# board.net
KiCad netlist of a schematic drawn in EAGLE
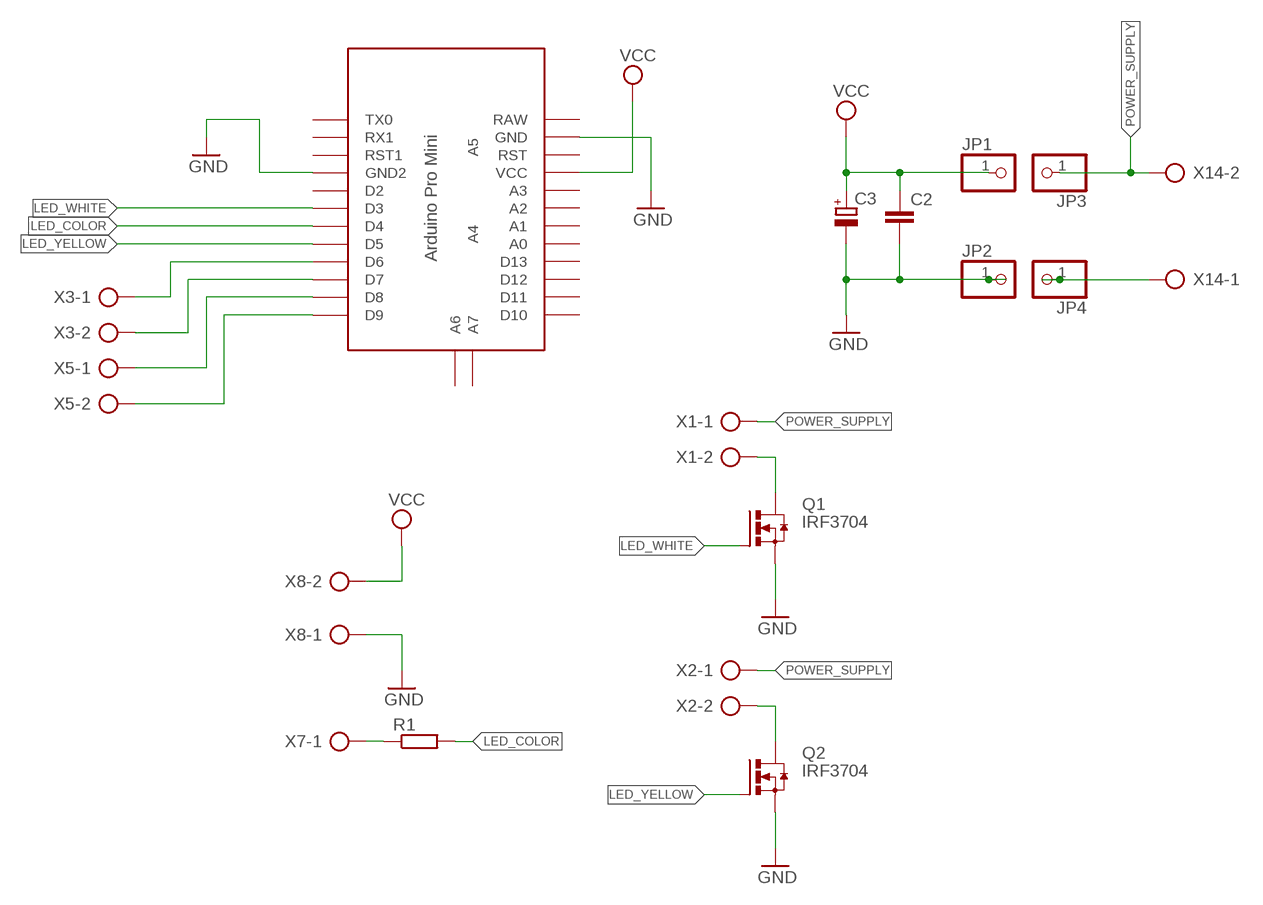
[diagram p0: schematic, sheet 1]

(export (version "E")
  (design (tool "Eeschema 10.0.6"))
  (components
    (comp (ref "C2")
      (value "C-EU050-025X075")
      (footprint "eagle-import:C050-025X075")
      (libsource (lib "eagle-import") (part "C-EU050-025X075"))
    )
    (comp (ref "C3")
      (value "CPOL-EUE3.5-8")
      (footprint "eagle-import:E3,5-8")
      (libsource (lib "eagle-import") (part "CPOL-EUE3.5-8"))
    )
    (comp (ref "JP1")
      (value "PINHD-1X1")
      (footprint "eagle-import:1X01")
      (libsource (lib "eagle-import") (part "PINHD-1X1"))
    )
    (comp (ref "JP2")
      (value "PINHD-1X1")
      (footprint "eagle-import:1X01")
      (libsource (lib "eagle-import") (part "PINHD-1X1"))
    )
    (comp (ref "JP3")
      (value "PINHD-1X1")
      (footprint "eagle-import:1X01")
      (libsource (lib "eagle-import") (part "PINHD-1X1"))
    )
    (comp (ref "JP4")
      (value "PINHD-1X1")
      (footprint "eagle-import:1X01")
      (libsource (lib "eagle-import") (part "PINHD-1X1"))
    )
    (comp (ref "Q1")
      (value "IRF3704")
      (footprint "eagle-import:TO220AH")
      (libsource (lib "eagle-import") (part "IRF3704"))
    )
    (comp (ref "Q2")
      (value "IRF3704")
      (footprint "eagle-import:TO220AH")
      (libsource (lib "eagle-import") (part "IRF3704"))
    )
    (comp (ref "R1")
      (value "R-EU_0204/7")
      (footprint "eagle-import:0204_7")
      (libsource (lib "eagle-import") (part "R-EU_0204/7"))
    )
    (comp (ref "U$1")
      (value "ABK-PRO-MINI")
      (footprint "eagle-import:ABK-PRO-MINI")
      (libsource (lib "eagle-import") (part "ABK-PRO-MINI"))
    )
    (comp (ref "X1")
      (value "AK500/2-H")
      (footprint "eagle-import:AK500_2-H")
      (libsource (lib "eagle-import") (part "AK500/2-H"))
    )
    (comp (ref "X2")
      (value "AK500/2-H")
      (footprint "eagle-import:AK500_2-H")
      (libsource (lib "eagle-import") (part "AK500/2-H"))
    )
    (comp (ref "X3")
      (value "AK500/2-H")
      (footprint "eagle-import:AK500_2-H")
      (libsource (lib "eagle-import") (part "AK500/2-H"))
    )
    (comp (ref "X5")
      (value "AK500/2-H")
      (footprint "eagle-import:AK500_2-H")
      (libsource (lib "eagle-import") (part "AK500/2-H"))
    )
    (comp (ref "X7")
      (value "AK500/2-H")
      (footprint "eagle-import:AK500_2-H")
      (libsource (lib "eagle-import") (part "AK500/2-H"))
    )
    (comp (ref "X8")
      (value "AK500/2-H")
      (footprint "eagle-import:AK500_2-H")
      (libsource (lib "eagle-import") (part "AK500/2-H"))
    )
    (comp (ref "X14")
      (value "AK500/2-H")
      (footprint "eagle-import:AK500_2-H")
      (libsource (lib "eagle-import") (part "AK500/2-H"))
    )
  )
  (nets
    (net (code "1") (name "GND") (class "Default")
      (node (ref "C2") (pin "2") (pinfunction "2_2") (pintype "passive"))
      (node (ref "C3") (pin "-") (pinfunction "-_-") (pintype "passive"))
      (node (ref "JP2") (pin "1") (pinfunction "1_1") (pintype "passive"))
      (node (ref "JP4") (pin "1") (pinfunction "1_1") (pintype "passive"))
      (node (ref "Q1") (pin "E") (pinfunction "S_E") (pintype "passive"))
      (node (ref "Q2") (pin "E") (pinfunction "S_E") (pintype "passive"))
      (node (ref "U$1") (pin "GND") (pinfunction "GND_GND") (pintype "bidirectional"))
      (node (ref "U$1") (pin "GND1") (pinfunction "GND2_GND1") (pintype "bidirectional"))
      (node (ref "X14") (pin "1") (pinfunction "KL_1") (pintype "passive"))
      (node (ref "X8") (pin "1") (pinfunction "KL_1") (pintype "passive"))
    )
    (net (code "2") (name "LED_COLOR") (class "Default")
      (node (ref "R1") (pin "2") (pinfunction "2_2") (pintype "passive"))
      (node (ref "U$1") (pin "D4") (pinfunction "D4_D4") (pintype "bidirectional"))
    )
    (net (code "3") (name "LED_WHITE") (class "Default")
      (node (ref "Q1") (pin "B") (pinfunction "G_B") (pintype "passive"))
      (node (ref "U$1") (pin "D3") (pinfunction "D3_D3") (pintype "bidirectional"))
    )
    (net (code "4") (name "LED_YELLOW") (class "Default")
      (node (ref "Q2") (pin "B") (pinfunction "G_B") (pintype "passive"))
      (node (ref "U$1") (pin "D5") (pinfunction "D5_D5") (pintype "bidirectional"))
    )
    (net (code "5") (name "Net-(Q1-D)") (class "Default")
      (node (ref "Q1") (pin "C") (pinfunction "D_C") (pintype "passive"))
      (node (ref "X1") (pin "2") (pinfunction "KL_2") (pintype "passive"))
    )
    (net (code "6") (name "Net-(Q2-D)") (class "Default")
      (node (ref "Q2") (pin "C") (pinfunction "D_C") (pintype "passive"))
      (node (ref "X2") (pin "2") (pinfunction "KL_2") (pintype "passive"))
    )
    (net (code "7") (name "Net-(X3A-KL)") (class "Default")
      (node (ref "U$1") (pin "D6") (pinfunction "D6_D6") (pintype "bidirectional"))
      (node (ref "X3") (pin "1") (pinfunction "KL_1") (pintype "passive"))
    )
    (net (code "8") (name "Net-(X3B-KL)") (class "Default")
      (node (ref "U$1") (pin "D7") (pinfunction "D7_D7") (pintype "bidirectional"))
      (node (ref "X3") (pin "2") (pinfunction "KL_2") (pintype "passive"))
    )
    (net (code "9") (name "Net-(X5A-KL)") (class "Default")
      (node (ref "U$1") (pin "D8") (pinfunction "D8_D8") (pintype "bidirectional"))
      (node (ref "X5") (pin "1") (pinfunction "KL_1") (pintype "passive"))
    )
    (net (code "10") (name "Net-(X5B-KL)") (class "Default")
      (node (ref "U$1") (pin "D9") (pinfunction "D9_D9") (pintype "bidirectional"))
      (node (ref "X5") (pin "2") (pinfunction "KL_2") (pintype "passive"))
    )
    (net (code "11") (name "Net-(X7A-KL)") (class "Default")
      (node (ref "R1") (pin "1") (pinfunction "1_1") (pintype "passive"))
      (node (ref "X7") (pin "1") (pinfunction "KL_1") (pintype "passive"))
    )
    (net (code "12") (name "POWER_SUPPLY") (class "Default")
      (node (ref "JP3") (pin "1") (pinfunction "1_1") (pintype "passive"))
      (node (ref "X1") (pin "1") (pinfunction "KL_1") (pintype "passive"))
      (node (ref "X14") (pin "2") (pinfunction "KL_2") (pintype "passive"))
      (node (ref "X2") (pin "1") (pinfunction "KL_1") (pintype "passive"))
    )
    (net (code "13") (name "VCC") (class "Default")
      (node (ref "C2") (pin "1") (pinfunction "1_1") (pintype "passive"))
      (node (ref "C3") (pin "+") (pinfunction "+_+") (pintype "passive"))
      (node (ref "JP1") (pin "1") (pinfunction "1_1") (pintype "passive"))
      (node (ref "U$1") (pin "VCC") (pinfunction "VCC_VCC") (pintype "bidirectional"))
      (node (ref "X8") (pin "2") (pinfunction "KL_2") (pintype "passive"))
    )
    (net (code "14") (name "unconnected-(U$1-PadA0)") (class "Default")
      (node (ref "U$1") (pin "A0") (pinfunction "A0_A0") (pintype "bidirectional"))
    )
    (net (code "15") (name "unconnected-(U$1-PadA1)") (class "Default")
      (node (ref "U$1") (pin "A1") (pinfunction "A1_A1") (pintype "bidirectional"))
    )
    (net (code "16") (name "unconnected-(U$1-PadA2)") (class "Default")
      (node (ref "U$1") (pin "A2") (pinfunction "A2_A2") (pintype "bidirectional"))
    )
    (net (code "17") (name "unconnected-(U$1-PadA3)") (class "Default")
      (node (ref "U$1") (pin "A3") (pinfunction "A3_A3") (pintype "bidirectional"))
    )
    (net (code "18") (name "unconnected-(U$1-PadA4)") (class "Default")
      (node (ref "U$1") (pin "A4") (pinfunction "A4_A4") (pintype "bidirectional"))
    )
    (net (code "19") (name "unconnected-(U$1-PadA5)") (class "Default")
      (node (ref "U$1") (pin "A5") (pinfunction "A5_A5") (pintype "bidirectional"))
    )
    (net (code "20") (name "unconnected-(U$1-PadA6)") (class "Default")
      (node (ref "U$1") (pin "A6") (pinfunction "A6_A6") (pintype "bidirectional"))
    )
    (net (code "21") (name "unconnected-(U$1-PadA7)") (class "Default")
      (node (ref "U$1") (pin "A7") (pinfunction "A7_A7") (pintype "bidirectional"))
    )
    (net (code "22") (name "unconnected-(U$1-PadD2)") (class "Default")
      (node (ref "U$1") (pin "D2") (pinfunction "D2_D2") (pintype "bidirectional"))
    )
    (net (code "23") (name "unconnected-(U$1-PadD10)") (class "Default")
      (node (ref "U$1") (pin "D10") (pinfunction "D10_D10") (pintype "bidirectional"))
    )
    (net (code "24") (name "unconnected-(U$1-PadD11)") (class "Default")
      (node (ref "U$1") (pin "D11") (pinfunction "D11_D11") (pintype "bidirectional"))
    )
    (net (code "25") (name "unconnected-(U$1-PadD12)") (class "Default")
      (node (ref "U$1") (pin "D12") (pinfunction "D12_D12") (pintype "bidirectional"))
    )
    (net (code "26") (name "unconnected-(U$1-PadD13)") (class "Default")
      (node (ref "U$1") (pin "D13") (pinfunction "D13_D13") (pintype "bidirectional"))
    )
    (net (code "27") (name "unconnected-(U$1-PadRAW)") (class "Default")
      (node (ref "U$1") (pin "RAW") (pinfunction "RAW_RAW") (pintype "bidirectional"))
    )
    (net (code "28") (name "unconnected-(U$1-PadRST)") (class "Default")
      (node (ref "U$1") (pin "RST") (pinfunction "RST_RST") (pintype "bidirectional"))
    )
    (net (code "29") (name "unconnected-(U$1-PadRST1)") (class "Default")
      (node (ref "U$1") (pin "RST1") (pinfunction "RST1_RST1") (pintype "bidirectional"))
    )
    (net (code "30") (name "unconnected-(U$1-PadRX1)") (class "Default")
      (node (ref "U$1") (pin "RX1") (pinfunction "RX1_RX1") (pintype "bidirectional"))
    )
    (net (code "31") (name "unconnected-(U$1-PadTX0)") (class "Default")
      (node (ref "U$1") (pin "TX0") (pinfunction "TX0_TX0") (pintype "bidirectional"))
    )
  )
)
